# ProPrj_bl_fucker_2025-07-29.net
KiCad netlist of a schematic drawn in EasyEDA Pro
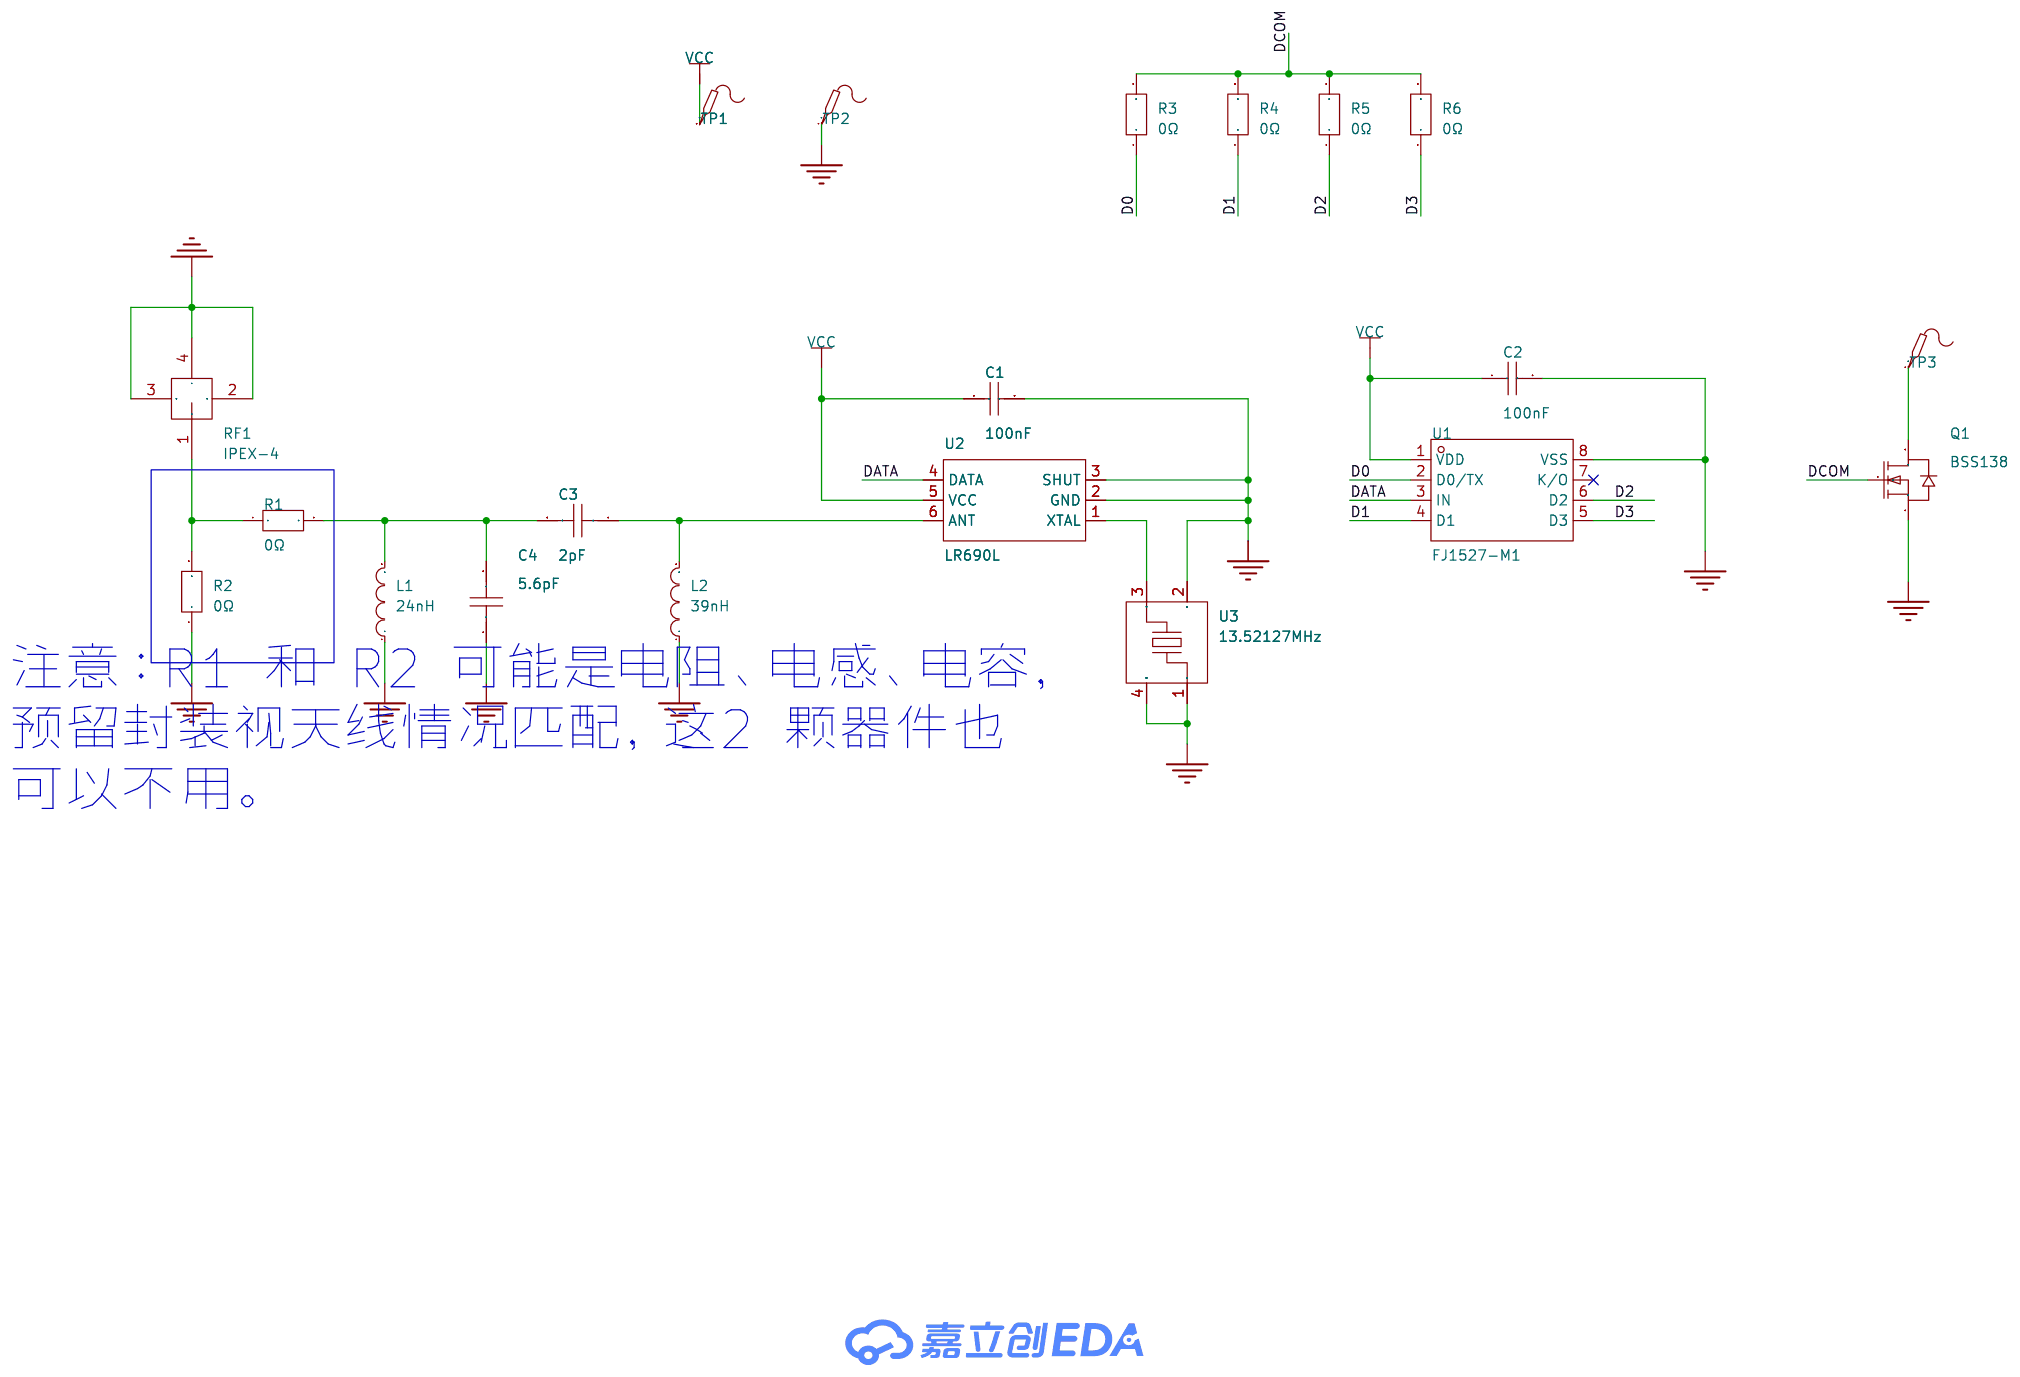
[diagram p0: schematic sheet]

(export (version "E")
  (design (tool "Eeschema 10.0.6"))
  (components
    (comp (ref "C1")
      (value "100nF")
      (footprint "easyedapro:C0201")
      (description "容值:100nF;精度:±10%;额定电压:25V;温度系数:X5R;")
      (fields
        (field (name "Manufacturer Part") "GRM033R61E104KE14D")
        (field (name "Manufacturer") "muRata(村田)")
      )
      (libsource (lib "easyedapro") (part "GRM033R61E104KE14D"))
    )
    (comp (ref "C2")
      (value "100nF")
      (footprint "easyedapro:C0201")
      (description "容值:100nF;精度:±10%;额定电压:25V;温度系数:X5R;")
      (fields
        (field (name "Manufacturer Part") "GRM033R61E104KE14D")
        (field (name "Manufacturer") "muRata(村田)")
      )
      (libsource (lib "easyedapro") (part "GRM033R61E104KE14D"))
    )
    (comp (ref "C3")
      (value "2pF")
      (footprint "easyedapro:C0201")
      (description "容值:2pF;额定电压:50V;材质(温度系数):C0G;")
      (fields
        (field (name "Manufacturer Part") "GRM0335C1H2R0BA01D")
        (field (name "Manufacturer") "muRata(村田)")
      )
      (libsource (lib "easyedapro") (part "GRM0335C1H2R0BA01D"))
    )
    (comp (ref "C4")
      (value "5.6pF")
      (footprint "easyedapro:C0201")
      (description "容值:5.6pF;额定电压:25V;材质(温度系数):NP0;")
      (fields
        (field (name "Manufacturer Part") "CQ0201BRNPO8BN5R6")
        (field (name "Manufacturer") "YAGEO(国巨)")
      )
      (libsource (lib "easyedapro") (part "CQ0201BRNPO8BN5R6"))
    )
    (comp (ref "L1")
      (value "24nH")
      (footprint "easyedapro:L0201")
      (description "电感值:24nH;精度:±3%;额定电流:140mA;饱和电流(Isat):-;直流电阻(DCR):2.3Ω;")
      (fields (field (name "Manufacturer Part") "LQP03TN24NH02D") (field (name "Manufacturer") "muRata(村田)"))
      (libsource (lib "easyedapro") (part "LQP03TN24NH02D"))
    )
    (comp (ref "L2")
      (value "39nH")
      (footprint "easyedapro:L0201")
      (description "电感值:39nH;精度:±10%;额定电流:100mA;饱和电流(Isat):-;直流电阻(DCR):2.3Ω;")
      (fields (field (name "Manufacturer Part") "VHF060303HQ39NKT") (field (name "Manufacturer") "FH(风华)"))
      (libsource (lib "easyedapro") (part "VHF060303HQ39NKT"))
    )
    (comp (ref "Q1")
      (value "BSS138")
      (footprint "easyedapro:SOT-23-3_L2.9-W1.3-P1.90-LS2.4-BR")
      (fields (field (name "Manufacturer") "宏嘉诚"))
      (libsource (lib "easyedapro") (part "BSS138_C7420339"))
    )
    (comp (ref "R1")
      (value "0Ω")
      (footprint "easyedapro:R0201")
      (description "电阻类型:厚膜电阻;阻值:0Ω;精度:±1%;功率:50mW;工作电压:25V;")
      (fields
        (field (name "Manufacturer Part") "0201WMF0000TEE")
        (field (name "Manufacturer") "UNI-ROYAL(厚声)")
      )
      (libsource (lib "easyedapro") (part "0201WMF0000TEE"))
    )
    (comp (ref "R2")
      (value "0Ω")
      (footprint "easyedapro:R0201")
      (description "电阻类型:厚膜电阻;阻值:0Ω;精度:±1%;功率:50mW;工作电压:25V;")
      (fields
        (field (name "Manufacturer Part") "0201WMF0000TEE")
        (field (name "Manufacturer") "UNI-ROYAL(厚声)")
      )
      (libsource (lib "easyedapro") (part "0201WMF0000TEE"))
    )
    (comp (ref "R3")
      (value "0Ω")
      (footprint "easyedapro:R0201")
      (description "电阻类型:厚膜电阻;阻值:0Ω;精度:±1%;功率:50mW;工作电压:25V;")
      (fields
        (field (name "Manufacturer Part") "0201WMF0000TEE")
        (field (name "Manufacturer") "UNI-ROYAL(厚声)")
      )
      (libsource (lib "easyedapro") (part "0201WMF0000TEE"))
    )
    (comp (ref "R4")
      (value "0Ω")
      (footprint "easyedapro:R0201")
      (description "电阻类型:厚膜电阻;阻值:0Ω;精度:±1%;功率:50mW;工作电压:25V;")
      (fields
        (field (name "Manufacturer Part") "0201WMF0000TEE")
        (field (name "Manufacturer") "UNI-ROYAL(厚声)")
      )
      (libsource (lib "easyedapro") (part "0201WMF0000TEE"))
    )
    (comp (ref "R5")
      (value "0Ω")
      (footprint "easyedapro:R0201")
      (description "电阻类型:厚膜电阻;阻值:0Ω;精度:±1%;功率:50mW;工作电压:25V;")
      (fields
        (field (name "Manufacturer Part") "0201WMF0000TEE")
        (field (name "Manufacturer") "UNI-ROYAL(厚声)")
      )
      (libsource (lib "easyedapro") (part "0201WMF0000TEE"))
    )
    (comp (ref "R6")
      (value "0Ω")
      (footprint "easyedapro:R0201")
      (description "电阻类型:厚膜电阻;阻值:0Ω;精度:±1%;功率:50mW;工作电压:25V;")
      (fields
        (field (name "Manufacturer Part") "0201WMF0000TEE")
        (field (name "Manufacturer") "UNI-ROYAL(厚声)")
      )
      (libsource (lib "easyedapro") (part "0201WMF0000TEE"))
    )
    (comp (ref "RF1")
      (value "IPEX-4")
      (footprint "easyedapro:IPEX-SMD_4P-L1.8-W1.7-LS2.0")
      (description "射频系列:IPEX;")
      (fields (field (name "Manufacturer") "Ziisor(致哲)"))
      (libsource (lib "easyedapro") (part "IPEX-4"))
    )
    (comp (ref "TP1")
      (value "~")
      (footprint "easyedapro:Test-Point-0.5mm")
      (description "Test Point 测试点")
      (libsource (lib "easyedapro") (part "Test-Point"))
    )
    (comp (ref "TP2")
      (value "~")
      (footprint "easyedapro:Test-Point-0.5mm")
      (description "Test Point 测试点")
      (libsource (lib "easyedapro") (part "Test-Point"))
    )
    (comp (ref "TP3")
      (value "~")
      (footprint "easyedapro:Test-Point-0.5mm")
      (description "Test Point 测试点")
      (libsource (lib "easyedapro") (part "Test-Point"))
    )
    (comp (ref "U1")
      (value "FJ1527-M1")
      (footprint "easyedapro:SOP-8_L4.9-W3.9-P1.27-LS6.0-BL-1")
      (description "RF遥控专用解码芯片")
      (fields (field (name "Manufacturer") "蜂鸟无线"))
      (libsource (lib "easyedapro") (part "FJ1527-M1"))
    )
    (comp (ref "U2")
      (value "LR690L")
      (footprint "easyedapro:SOT-23-6_L2.9-W1.6-P0.95-LS2.8-BL")
      (description "频率范围:300MHz~440MHz;灵敏度:-110dBm;")
      (fields (field (name "Manufacturer") "蜂鸟无线"))
      (libsource (lib "easyedapro") (part "LR690L"))
    )
    (comp (ref "U3")
      (value "13.52127MHz")
      (footprint "easyedapro:CRYSTAL-SMD_4P-L3.2-W2.5-BL")
      (description "晶振类型:贴片晶振;频率:13.52127MHz;常温频差:±10ppm;负载电容:20pF;频率稳定度:±20ppm;")
      (fields
        (field (name "Manufacturer Part") "TAXM13.52127M4RLBDDT2T")
        (field (name "Manufacturer") "YJX(雅晶鑫)")
      )
      (libsource (lib "easyedapro") (part "TAXM13.52127M4RLBDDT2T"))
    )
  )
  (nets
    (net (code "1") (name "/D0") (class "Default")
      (node (ref "R3") (pin "1") (pinfunction "1_1") (pintype "unspecified"))
      (node (ref "U1") (pin "2") (pinfunction "D0/TX_2") (pintype "unspecified"))
    )
    (net (code "2") (name "/D1") (class "Default")
      (node (ref "R4") (pin "1") (pinfunction "1_1") (pintype "unspecified"))
      (node (ref "U1") (pin "4") (pinfunction "D1_4") (pintype "unspecified"))
    )
    (net (code "3") (name "/D2") (class "Default")
      (node (ref "R5") (pin "1") (pinfunction "1_1") (pintype "unspecified"))
      (node (ref "U1") (pin "6") (pinfunction "D2_6") (pintype "unspecified"))
    )
    (net (code "4") (name "/D3") (class "Default")
      (node (ref "R6") (pin "1") (pinfunction "1_1") (pintype "unspecified"))
      (node (ref "U1") (pin "5") (pinfunction "D3_5") (pintype "unspecified"))
    )
    (net (code "5") (name "/DATA") (class "Default")
      (node (ref "U1") (pin "3") (pinfunction "IN_3") (pintype "unspecified"))
      (node (ref "U2") (pin "4") (pinfunction "DATA_4") (pintype "unspecified"))
    )
    (net (code "6") (name "/DCOM") (class "Default")
      (node (ref "Q1") (pin "1") (pinfunction "G_1") (pintype "unspecified"))
      (node (ref "R3") (pin "2") (pinfunction "2_2") (pintype "unspecified"))
      (node (ref "R4") (pin "2") (pinfunction "2_2") (pintype "unspecified"))
      (node (ref "R5") (pin "2") (pinfunction "2_2") (pintype "unspecified"))
      (node (ref "R6") (pin "2") (pinfunction "2_2") (pintype "unspecified"))
    )
    (net (code "7") (name "GND") (class "Default")
      (node (ref "C1") (pin "2") (pinfunction "2_2") (pintype "input"))
      (node (ref "C2") (pin "2") (pinfunction "2_2") (pintype "input"))
      (node (ref "C4") (pin "1") (pinfunction "1_1") (pintype "unspecified"))
      (node (ref "L1") (pin "1") (pinfunction "1_1") (pintype "unspecified"))
      (node (ref "L2") (pin "1") (pinfunction "1_1") (pintype "unspecified"))
      (node (ref "Q1") (pin "2") (pinfunction "S_2") (pintype "unspecified"))
      (node (ref "R2") (pin "1") (pinfunction "1_1") (pintype "unspecified"))
      (node (ref "RF1") (pin "2") (pinfunction "2_2") (pintype "unspecified"))
      (node (ref "RF1") (pin "3") (pinfunction "3_3") (pintype "unspecified"))
      (node (ref "RF1") (pin "4") (pinfunction "4_4") (pintype "unspecified"))
      (node (ref "TP2") (pin "1") (pinfunction "1_1") (pintype "input"))
      (node (ref "U1") (pin "8") (pinfunction "VSS_8") (pintype "unspecified"))
      (node (ref "U2") (pin "2") (pinfunction "GND_2") (pintype "unspecified"))
      (node (ref "U2") (pin "3") (pinfunction "SHUT_3") (pintype "unspecified"))
      (node (ref "U3") (pin "1") (pinfunction "1_1") (pintype "input"))
      (node (ref "U3") (pin "2") (pinfunction "GND_2") (pintype "input"))
      (node (ref "U3") (pin "4") (pinfunction "GND_4") (pintype "input"))
    )
    (net (code "8") (name "Net-(C3-Pad2)") (class "Default")
      (node (ref "C3") (pin "2") (pinfunction "2_2") (pintype "unspecified"))
      (node (ref "C4") (pin "2") (pinfunction "2_2") (pintype "unspecified"))
      (node (ref "L1") (pin "2") (pinfunction "2_2") (pintype "unspecified"))
      (node (ref "R1") (pin "2") (pinfunction "2_2") (pintype "unspecified"))
    )
    (net (code "9") (name "Net-(Q1-D)") (class "Default")
      (node (ref "Q1") (pin "3") (pinfunction "D_3") (pintype "unspecified"))
      (node (ref "TP3") (pin "1") (pinfunction "1_1") (pintype "input"))
    )
    (net (code "10") (name "Net-(R1-Pad1)") (class "Default")
      (node (ref "R1") (pin "1") (pinfunction "1_1") (pintype "unspecified"))
      (node (ref "R2") (pin "2") (pinfunction "2_2") (pintype "unspecified"))
      (node (ref "RF1") (pin "1") (pinfunction "1_1") (pintype "unspecified"))
    )
    (net (code "11") (name "Net-(U2-ANT)") (class "Default")
      (node (ref "C3") (pin "1") (pinfunction "1_1") (pintype "unspecified"))
      (node (ref "L2") (pin "2") (pinfunction "2_2") (pintype "unspecified"))
      (node (ref "U2") (pin "6") (pinfunction "ANT_6") (pintype "unspecified"))
    )
    (net (code "12") (name "Net-(U2-XTAL)") (class "Default")
      (node (ref "U2") (pin "1") (pinfunction "XTAL_1") (pintype "unspecified"))
      (node (ref "U3") (pin "3") (pinfunction "3_3") (pintype "input"))
    )
    (net (code "13") (name "VCC") (class "Default")
      (node (ref "C1") (pin "1") (pinfunction "1_1") (pintype "input"))
      (node (ref "C2") (pin "1") (pinfunction "1_1") (pintype "input"))
      (node (ref "TP1") (pin "1") (pinfunction "1_1") (pintype "input"))
      (node (ref "U1") (pin "1") (pinfunction "VDD_1") (pintype "unspecified"))
      (node (ref "U2") (pin "5") (pinfunction "VCC_5") (pintype "unspecified"))
    )
    (net (code "14") (name "unconnected-(U1-K{slash}O-Pad7)") (class "Default")
      (node (ref "U1") (pin "7") (pinfunction "K/O_7") (pintype "unspecified+no_connect"))
    )
  )
)
